# Sheet1.net
KiCad netlist of a schematic drawn in Altium Designer
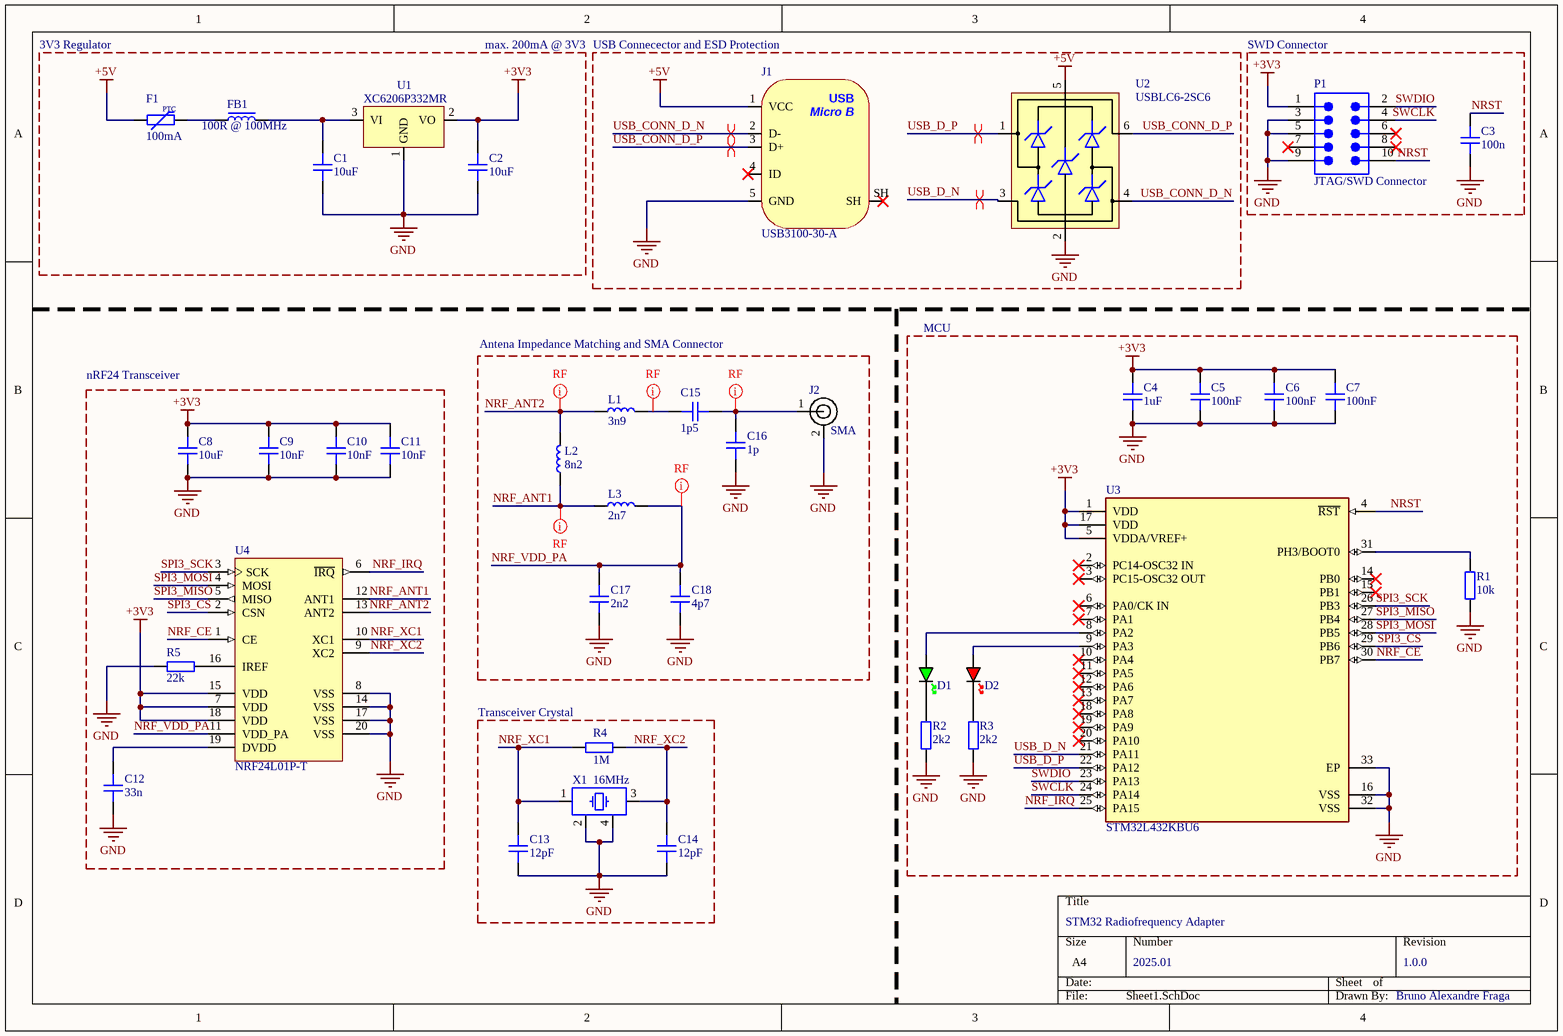
[diagram p0: Sheet1.SchDoc]

(export (version "E")
  (design (tool "Eeschema 10.0.6"))
  (components
    (comp (ref "C1")
      (value "10uF")
      (footprint "CAP_0603")
      (description "Capacitor SMD 0603")
      (libsource (lib "FragasLab") (part "CAP_0603"))
    )
    (comp (ref "C2")
      (value "10uF")
      (footprint "CAP_0603")
      (description "Capacitor SMD 0603")
      (libsource (lib "FragasLab") (part "CAP_0603"))
    )
    (comp (ref "C3")
      (value "100n")
      (footprint "CAP_0402")
      (description "Capacitor SMD 0402")
      (libsource (lib "FragasLab") (part "CAP_0402"))
    )
    (comp (ref "C4")
      (value "1uF")
      (footprint "CAP_0402")
      (description "Capacitor SMD 0402")
      (libsource (lib "FragasLab") (part "CAP_0402"))
    )
    (comp (ref "C5")
      (value "100nF")
      (footprint "CAP_0402")
      (description "Capacitor SMD 0402")
      (libsource (lib "FragasLab") (part "CAP_0402"))
    )
    (comp (ref "C6")
      (value "100nF")
      (footprint "CAP_0402")
      (description "Capacitor SMD 0402")
      (libsource (lib "FragasLab") (part "CAP_0402"))
    )
    (comp (ref "C7")
      (value "100nF")
      (footprint "CAP_0402")
      (description "Capacitor SMD 0402")
      (libsource (lib "FragasLab") (part "CAP_0402"))
    )
    (comp (ref "C8")
      (value "10uF")
      (footprint "CAP_0402")
      (description "Capacitor SMD 0402")
      (libsource (lib "FragasLab") (part "CAP_0402"))
    )
    (comp (ref "C9")
      (value "10nF")
      (footprint "CAP_0402")
      (description "Capacitor SMD 0402")
      (libsource (lib "FragasLab") (part "CAP_0402"))
    )
    (comp (ref "C10")
      (value "10nF")
      (footprint "CAP_0402")
      (description "Capacitor SMD 0402")
      (libsource (lib "FragasLab") (part "CAP_0402"))
    )
    (comp (ref "C11")
      (value "10nF")
      (footprint "CAP_0402")
      (description "Capacitor SMD 0402")
      (libsource (lib "FragasLab") (part "CAP_0402"))
    )
    (comp (ref "C12")
      (value "33n")
      (footprint "CAP_0402")
      (description "Capacitor SMD 0402")
      (libsource (lib "FragasLab") (part "CAP_0402"))
    )
    (comp (ref "C13")
      (value "12pF")
      (footprint "CAP_0402")
      (description "Capacitor SMD 0402")
      (libsource (lib "FragasLab") (part "CAP_0402"))
    )
    (comp (ref "C14")
      (value "12pF")
      (footprint "CAP_0402")
      (description "Capacitor SMD 0402")
      (libsource (lib "FragasLab") (part "CAP_0402"))
    )
    (comp (ref "C15")
      (value "1p5")
      (footprint "CAP_0402")
      (description "Capacitor SMD 0402")
      (libsource (lib "FragasLab") (part "CAP_0402"))
    )
    (comp (ref "C16")
      (value "1p")
      (footprint "CAP_0402")
      (description "Capacitor SMD 0402")
      (libsource (lib "FragasLab") (part "CAP_0402"))
    )
    (comp (ref "C17")
      (value "2n2")
      (footprint "CAP_0402")
      (description "Capacitor SMD 0402")
      (libsource (lib "FragasLab") (part "CAP_0402"))
    )
    (comp (ref "C18")
      (value "4p7")
      (footprint "CAP_0402")
      (description "Capacitor SMD 0402")
      (libsource (lib "FragasLab") (part "CAP_0402"))
    )
    (comp (ref "D1")
      (value "GREEN")
      (footprint "LED_0402_GREEN")
      (description "LED 0402 GREEN SMD")
      (libsource (lib "FragasLab") (part "LED_0402_GREEN"))
    )
    (comp (ref "D2")
      (value "RED")
      (footprint "LED_0402_RED")
      (description "LED 0402 RED SMD")
      (libsource (lib "FragasLab") (part "LED_0402_RED"))
    )
    (comp (ref "F1")
      (value "100mA")
      (footprint "FUSE_1206")
      (description "Fuse PPTC SMD 1206")
      (libsource (lib "FragasLab") (part "FUSE_PPTC_1206"))
    )
    (comp (ref "FB1")
      (value "100R @ 100MHz")
      (footprint "FB_0805")
      (description "Ferrite Bead SMD 0805")
      (libsource (lib "FragasLab") (part "FB_0805"))
    )
    (comp (ref "J1")
      (value "USB3100-30-A")
      (footprint "USB3100-30-A")
      (description "USB Connector Type Micro B 2.0 SMD Reverse Mount")
      (fields (field (name "MANUFACTURER") "GCT"))
      (libsource (lib "FragasLab") (part "USB3100-30-A"))
    )
    (comp (ref "J2")
      (value "SMA")
      (footprint "73251-1150")
      (description "RF Connector 50 Ohms, SMA Jack Receptacle, Edge Mount, .25µm Gold (Au) Plating")
      (fields (field (name "MANUFACTURER") "Molex") (field (name "MANUFACTURER PART NUMBER") "73251-1150"))
      (libsource (lib "FragasLab") (part "73251-1150"))
    )
    (comp (ref "L1")
      (value "3n9")
      (footprint "IND_0402")
      (description "Inductor SMD 0402")
      (libsource (lib "FragasLab") (part "IND_0402"))
    )
    (comp (ref "L2")
      (value "8n2")
      (footprint "IND_0402")
      (description "Inductor SMD 0402")
      (libsource (lib "FragasLab") (part "IND_0402"))
    )
    (comp (ref "L3")
      (value "2n7")
      (footprint "IND_0402")
      (description "Inductor SMD 0402")
      (libsource (lib "FragasLab") (part "IND_0402"))
    )
    (comp (ref "P1")
      (value "JTAG/SWD Connector")
      (footprint "61201021621")
      (libsource (lib "FragasLab") (part "CON-JTAG-Box"))
    )
    (comp (ref "R1")
      (value "10k")
      (footprint "RES_0402")
      (description "Resistor SMD 0402")
      (libsource (lib "FragasLab") (part "RES_0402"))
    )
    (comp (ref "R2")
      (value "2k2")
      (footprint "RES_0603")
      (description "Resistor SMD 0603")
      (libsource (lib "FragasLab") (part "RES_0603"))
    )
    (comp (ref "R3")
      (value "2k2")
      (footprint "RES_0603")
      (description "Resistor SMD 0603")
      (libsource (lib "FragasLab") (part "RES_0603"))
    )
    (comp (ref "R4")
      (value "1M")
      (footprint "RES_0402")
      (description "Resistor SMD 0402")
      (libsource (lib "FragasLab") (part "RES_0402"))
    )
    (comp (ref "R5")
      (value "22k")
      (footprint "RES_0402")
      (description "Resistor SMD 0402")
      (libsource (lib "FragasLab") (part "RES_0402"))
    )
    (comp (ref "U1")
      (value "XC6206P332MR")
      (footprint "SOT95P240X115-3N")
      (description "Linear voltage regulator 250mA;\r\nOutput voltage: 1.5V~5.0V (step size 0.1V).")
      (libsource (lib "FragasLab") (part "XC6206P332MR"))
    )
    (comp (ref "U2")
      (value "USBLC6-2SC6")
      (footprint "SOT-23-6")
      (description "Low-Capacitance ESD Protection USB")
      (fields (field (name "MANUFACTURER") "STMicroelectronics"))
      (libsource (lib "FragasLab") (part "USBLC6-2SC6"))
    )
    (comp (ref "U3")
      (value "STM32L432KBU6")
      (footprint "FP-UFQFPN32-A0B8-MFG")
      (fields
        (field (name "MANUFACTURER") "STMicroelectronics")
        (field (name "OCTOPART") "https://octopart.com/stm32l432kbu6-stmicroelectronics-74568735")
      )
      (libsource (lib "FragasLab") (part "STM32L432KBU6"))
    )
    (comp (ref "U4")
      (value "NRF24L01P-T")
      (footprint "NRSC-QFN-20_L")
      (description "Single Chip Transceiver, 2.4 GHz, 60 mW, 1.9 to 3.6 V, -40 to 85 degC, 20-Pin QFN, RoHS, Tray")
      (fields (field (name "MANUFACTURER") "Nordic Semiconductor"))
      (libsource (lib "FragasLab") (part "nRF24L01"))
    )
    (comp (ref "X1")
      (value "16MHz")
      (footprint "XTAL_2016")
      (description "Crystal SMD 4-Pin 2.0x1.6mm")
      (libsource (lib "FragasLab") (part "XTAL_2016"))
    )
  )
  (nets
    (net (code "1") (name "+3V3") (class "Default")
      (node (ref "C10") (pin "2") (pinfunction "2_2") (pintype "passive"))
      (node (ref "C11") (pin "2") (pinfunction "2_2") (pintype "passive"))
      (node (ref "C2") (pin "1") (pinfunction "1_1") (pintype "passive"))
      (node (ref "C4") (pin "2") (pinfunction "2_2") (pintype "passive"))
      (node (ref "C5") (pin "2") (pinfunction "2_2") (pintype "passive"))
      (node (ref "C6") (pin "2") (pinfunction "2_2") (pintype "passive"))
      (node (ref "C7") (pin "2") (pinfunction "2_2") (pintype "passive"))
      (node (ref "C8") (pin "2") (pinfunction "2_2") (pintype "passive"))
      (node (ref "C9") (pin "2") (pinfunction "2_2") (pintype "passive"))
      (node (ref "P1") (pin "1") (pinfunction "1_1") (pintype "passive"))
      (node (ref "U1") (pin "2") (pinfunction "VO_2") (pintype "passive"))
      (node (ref "U3") (pin "1") (pinfunction "VDD_1") (pintype "power_in"))
      (node (ref "U3") (pin "17") (pinfunction "VDD_17") (pintype "power_in"))
      (node (ref "U3") (pin "5") (pinfunction "VDDA/VREF+_5") (pintype "power_in"))
      (node (ref "U4") (pin "15") (pinfunction "VDD_15") (pintype "power_in"))
      (node (ref "U4") (pin "18") (pinfunction "VDD_18") (pintype "power_in"))
      (node (ref "U4") (pin "7") (pinfunction "VDD_7") (pintype "power_in"))
    )
    (net (code "2") (name "+5V") (class "Default")
      (node (ref "F1") (pin "1") (pinfunction "1_1") (pintype "passive"))
      (node (ref "J1") (pin "1") (pinfunction "VCC_1") (pintype "passive"))
      (node (ref "U2") (pin "5") (pinfunction "VBUS_5") (pintype "power_in"))
    )
    (net (code "3") (name "/NRF_ANT1") (class "Default")
      (node (ref "L2") (pin "1") (pinfunction "1_1") (pintype "passive"))
      (node (ref "L3") (pin "1") (pinfunction "1_1") (pintype "passive"))
      (node (ref "U4") (pin "12") (pinfunction "ANT1_12") (pintype "passive"))
    )
    (net (code "4") (name "/NRF_ANT2") (class "Default")
      (node (ref "L1") (pin "1") (pinfunction "1_1") (pintype "passive"))
      (node (ref "L2") (pin "2") (pinfunction "2_2") (pintype "passive"))
      (node (ref "U4") (pin "13") (pinfunction "ANT2_13") (pintype "passive"))
    )
    (net (code "5") (name "/NRF_CE") (class "Default")
      (node (ref "U3") (pin "30") (pinfunction "PB7_30") (pintype "bidirectional"))
      (node (ref "U4") (pin "1") (pinfunction "CE_1") (pintype "input"))
    )
    (net (code "6") (name "/NRF_IRQ") (class "Default")
      (node (ref "U3") (pin "25") (pinfunction "PA15_25") (pintype "bidirectional"))
      (node (ref "U4") (pin "6") (pinfunction "~{IRQ}_6") (pintype "output"))
    )
    (net (code "7") (name "/NRF_VDD_PA") (class "Default")
      (node (ref "C17") (pin "2") (pinfunction "2_2") (pintype "passive"))
      (node (ref "C18") (pin "2") (pinfunction "2_2") (pintype "passive"))
      (node (ref "L3") (pin "2") (pinfunction "2_2") (pintype "passive"))
      (node (ref "U4") (pin "11") (pinfunction "VDD_PA_11") (pintype "power_in"))
    )
    (net (code "8") (name "/NRF_XC1") (class "Default")
      (node (ref "C13") (pin "2") (pinfunction "2_2") (pintype "passive"))
      (node (ref "R4") (pin "1") (pinfunction "1_1") (pintype "passive"))
      (node (ref "U4") (pin "10") (pinfunction "XC1_10") (pintype "passive"))
      (node (ref "X1") (pin "1") (pinfunction "1_1") (pintype "passive"))
    )
    (net (code "9") (name "/NRF_XC2") (class "Default")
      (node (ref "C14") (pin "2") (pinfunction "2_2") (pintype "passive"))
      (node (ref "R4") (pin "2") (pinfunction "2_2") (pintype "passive"))
      (node (ref "U4") (pin "9") (pinfunction "XC2_9") (pintype "passive"))
      (node (ref "X1") (pin "3") (pinfunction "3_3") (pintype "passive"))
    )
    (net (code "10") (name "/NRST") (class "Default")
      (node (ref "C3") (pin "2") (pinfunction "2_2") (pintype "passive"))
      (node (ref "P1") (pin "10") (pinfunction "10_10") (pintype "passive"))
      (node (ref "U3") (pin "4") (pinfunction "~{RST}_4") (pintype "input"))
    )
    (net (code "11") (name "/SPI3_CS") (class "Default")
      (node (ref "U3") (pin "29") (pinfunction "PB6_29") (pintype "bidirectional"))
      (node (ref "U4") (pin "2") (pinfunction "CSN_2") (pintype "input"))
    )
    (net (code "12") (name "/SPI3_MISO") (class "Default")
      (node (ref "U3") (pin "27") (pinfunction "PB4_27") (pintype "bidirectional"))
      (node (ref "U4") (pin "5") (pinfunction "MISO_5") (pintype "output"))
    )
    (net (code "13") (name "/SPI3_MOSI") (class "Default")
      (node (ref "U3") (pin "28") (pinfunction "PB5_28") (pintype "bidirectional"))
      (node (ref "U4") (pin "4") (pinfunction "MOSI_4") (pintype "input"))
    )
    (net (code "14") (name "/SPI3_SCK") (class "Default")
      (node (ref "U3") (pin "26") (pinfunction "PB3_26") (pintype "bidirectional"))
      (node (ref "U4") (pin "3") (pinfunction "SCK_3") (pintype "input"))
    )
    (net (code "15") (name "/SWCLK") (class "Default")
      (node (ref "P1") (pin "4") (pinfunction "4_4") (pintype "passive"))
      (node (ref "U3") (pin "24") (pinfunction "PA14_24") (pintype "bidirectional"))
    )
    (net (code "16") (name "/SWDIO") (class "Default")
      (node (ref "P1") (pin "2") (pinfunction "2_2") (pintype "passive"))
      (node (ref "U3") (pin "23") (pinfunction "PA13_23") (pintype "bidirectional"))
    )
    (net (code "17") (name "/USB_CONN_D_N") (class "Default")
      (node (ref "J1") (pin "2") (pinfunction "D-_2") (pintype "passive"))
      (node (ref "U2") (pin "4") (pinfunction "IO2_4") (pintype "bidirectional"))
    )
    (net (code "18") (name "/USB_CONN_D_P") (class "Default")
      (node (ref "J1") (pin "3") (pinfunction "D+_3") (pintype "passive"))
      (node (ref "U2") (pin "6") (pinfunction "IO1_6") (pintype "bidirectional"))
    )
    (net (code "19") (name "/USB_D_N") (class "Default")
      (node (ref "U2") (pin "3") (pinfunction "IO2_3") (pintype "bidirectional"))
      (node (ref "U3") (pin "21") (pinfunction "PA11_21") (pintype "bidirectional"))
    )
    (net (code "20") (name "/USB_D_P") (class "Default")
      (node (ref "U2") (pin "1") (pinfunction "IO1_1") (pintype "bidirectional"))
      (node (ref "U3") (pin "22") (pinfunction "PA12_22") (pintype "bidirectional"))
    )
    (net (code "21") (name "GND") (class "Default")
      (node (ref "C1") (pin "2") (pinfunction "2_2") (pintype "passive"))
      (node (ref "C10") (pin "1") (pinfunction "1_1") (pintype "passive"))
      (node (ref "C11") (pin "1") (pinfunction "1_1") (pintype "passive"))
      (node (ref "C12") (pin "1") (pinfunction "1_1") (pintype "passive"))
      (node (ref "C13") (pin "1") (pinfunction "1_1") (pintype "passive"))
      (node (ref "C14") (pin "1") (pinfunction "1_1") (pintype "passive"))
      (node (ref "C16") (pin "1") (pinfunction "1_1") (pintype "passive"))
      (node (ref "C17") (pin "1") (pinfunction "1_1") (pintype "passive"))
      (node (ref "C18") (pin "1") (pinfunction "1_1") (pintype "passive"))
      (node (ref "C2") (pin "2") (pinfunction "2_2") (pintype "passive"))
      (node (ref "C3") (pin "1") (pinfunction "1_1") (pintype "passive"))
      (node (ref "C4") (pin "1") (pinfunction "1_1") (pintype "passive"))
      (node (ref "C5") (pin "1") (pinfunction "1_1") (pintype "passive"))
      (node (ref "C6") (pin "1") (pinfunction "1_1") (pintype "passive"))
      (node (ref "C7") (pin "1") (pinfunction "1_1") (pintype "passive"))
      (node (ref "C8") (pin "1") (pinfunction "1_1") (pintype "passive"))
      (node (ref "C9") (pin "1") (pinfunction "1_1") (pintype "passive"))
      (node (ref "J1") (pin "5") (pinfunction "GND_5") (pintype "passive"))
      (node (ref "J2") (pin "2") (pinfunction "2_2") (pintype "passive"))
      (node (ref "P1") (pin "3") (pinfunction "3_3") (pintype "passive"))
      (node (ref "P1") (pin "5") (pinfunction "5_5") (pintype "passive"))
      (node (ref "P1") (pin "9") (pinfunction "9_9") (pintype "passive"))
      (node (ref "R1") (pin "1") (pinfunction "1_1") (pintype "passive"))
      (node (ref "R2") (pin "1") (pinfunction "1_1") (pintype "passive"))
      (node (ref "R3") (pin "1") (pinfunction "1_1") (pintype "passive"))
      (node (ref "R5") (pin "2") (pinfunction "2_2") (pintype "passive"))
      (node (ref "U1") (pin "1") (pinfunction "GND_1") (pintype "passive"))
      (node (ref "U2") (pin "2") (pinfunction "GND_2") (pintype "power_in"))
      (node (ref "U3") (pin "16") (pinfunction "VSS_16") (pintype "power_in"))
      (node (ref "U3") (pin "32") (pinfunction "VSS_32") (pintype "power_in"))
      (node (ref "U3") (pin "33") (pinfunction "EP_33") (pintype "power_in"))
      (node (ref "U4") (pin "14") (pinfunction "VSS_14") (pintype "power_in"))
      (node (ref "U4") (pin "17") (pinfunction "VSS_17") (pintype "power_in"))
      (node (ref "U4") (pin "20") (pinfunction "VSS_20") (pintype "power_in"))
      (node (ref "U4") (pin "8") (pinfunction "VSS_8") (pintype "power_in"))
      (node (ref "X1") (pin "2") (pinfunction "2_2") (pintype "passive"))
      (node (ref "X1") (pin "4") (pinfunction "4_4") (pintype "passive"))
    )
    (net (code "22") (name "Net-(C15-Pad1)") (class "Default")
      (node (ref "C15") (pin "1") (pinfunction "1_1") (pintype "passive"))
      (node (ref "L1") (pin "2") (pinfunction "2_2") (pintype "passive"))
    )
    (net (code "23") (name "Net-(C15-Pad2)") (class "Default")
      (node (ref "C15") (pin "2") (pinfunction "2_2") (pintype "passive"))
      (node (ref "C16") (pin "2") (pinfunction "2_2") (pintype "passive"))
      (node (ref "J2") (pin "1") (pinfunction "1_1") (pintype "passive"))
    )
    (net (code "24") (name "Net-(D1-PadK)") (class "Default")
      (node (ref "D1") (pin "K") (pinfunction "K_K") (pintype "passive"))
      (node (ref "R2") (pin "2") (pinfunction "2_2") (pintype "passive"))
    )
    (net (code "25") (name "Net-(D2-PadK)") (class "Default")
      (node (ref "D2") (pin "K") (pinfunction "K_K") (pintype "passive"))
      (node (ref "R3") (pin "2") (pinfunction "2_2") (pintype "passive"))
    )
    (net (code "26") (name "Net-(F1-Pad2)") (class "Default")
      (node (ref "F1") (pin "2") (pinfunction "2_2") (pintype "passive"))
      (node (ref "FB1") (pin "1") (pinfunction "1_1") (pintype "passive"))
    )
    (net (code "27") (name "Net-(U1-VI)") (class "Default")
      (node (ref "C1") (pin "1") (pinfunction "1_1") (pintype "passive"))
      (node (ref "FB1") (pin "2") (pinfunction "2_2") (pintype "passive"))
      (node (ref "U1") (pin "3") (pinfunction "VI_3") (pintype "passive"))
    )
    (net (code "28") (name "Net-(U3-PA2)") (class "Default")
      (node (ref "D1") (pin "A") (pinfunction "A_A") (pintype "passive"))
      (node (ref "U3") (pin "8") (pinfunction "PA2_8") (pintype "bidirectional"))
    )
    (net (code "29") (name "Net-(U3-PA3)") (class "Default")
      (node (ref "D2") (pin "A") (pinfunction "A_A") (pintype "passive"))
      (node (ref "U3") (pin "9") (pinfunction "PA3_9") (pintype "bidirectional"))
    )
    (net (code "30") (name "Net-(U3-PH3{slash}BOOT0)") (class "Default")
      (node (ref "R1") (pin "2") (pinfunction "2_2") (pintype "passive"))
      (node (ref "U3") (pin "31") (pinfunction "PH3/BOOT0_31") (pintype "bidirectional"))
    )
    (net (code "31") (name "Net-(U4-DVDD)") (class "Default")
      (node (ref "C12") (pin "2") (pinfunction "2_2") (pintype "passive"))
      (node (ref "U4") (pin "19") (pinfunction "DVDD_19") (pintype "power_in"))
    )
    (net (code "32") (name "Net-(U4-IREF)") (class "Default")
      (node (ref "R5") (pin "1") (pinfunction "1_1") (pintype "passive"))
      (node (ref "U4") (pin "16") (pinfunction "IREF_16") (pintype "passive"))
    )
    (net (code "33") (name "unconnected-(J1-ID-Pad4)") (class "Default")
      (node (ref "J1") (pin "4") (pinfunction "ID_4") (pintype "passive+no_connect"))
    )
    (net (code "34") (name "unconnected-(J1-PadSH)") (class "Default")
      (node (ref "J1") (pin "SH") (pinfunction "SH_SH") (pintype "passive+no_connect"))
    )
    (net (code "35") (name "unconnected-(P1-Pad6)") (class "Default")
      (node (ref "P1") (pin "6") (pinfunction "6_6") (pintype "passive+no_connect"))
    )
    (net (code "36") (name "unconnected-(P1-Pad7)") (class "Default")
      (node (ref "P1") (pin "7") (pinfunction "7_7") (pintype "passive+no_connect"))
    )
    (net (code "37") (name "unconnected-(P1-Pad8)") (class "Default")
      (node (ref "P1") (pin "8") (pinfunction "8_8") (pintype "passive+no_connect"))
    )
    (net (code "38") (name "unconnected-(U3-PA0{slash}CK_IN-Pad6)") (class "Default")
      (node (ref "U3") (pin "6") (pinfunction "PA0/CK_IN_6") (pintype "bidirectional+no_connect"))
    )
    (net (code "39") (name "unconnected-(U3-PA1-Pad7)") (class "Default")
      (node (ref "U3") (pin "7") (pinfunction "PA1_7") (pintype "bidirectional+no_connect"))
    )
    (net (code "40") (name "unconnected-(U3-PA4-Pad10)") (class "Default")
      (node (ref "U3") (pin "10") (pinfunction "PA4_10") (pintype "bidirectional+no_connect"))
    )
    (net (code "41") (name "unconnected-(U3-PA5-Pad11)") (class "Default")
      (node (ref "U3") (pin "11") (pinfunction "PA5_11") (pintype "bidirectional+no_connect"))
    )
    (net (code "42") (name "unconnected-(U3-PA6-Pad12)") (class "Default")
      (node (ref "U3") (pin "12") (pinfunction "PA6_12") (pintype "bidirectional+no_connect"))
    )
    (net (code "43") (name "unconnected-(U3-PA7-Pad13)") (class "Default")
      (node (ref "U3") (pin "13") (pinfunction "PA7_13") (pintype "bidirectional+no_connect"))
    )
    (net (code "44") (name "unconnected-(U3-PA8-Pad18)") (class "Default")
      (node (ref "U3") (pin "18") (pinfunction "PA8_18") (pintype "bidirectional+no_connect"))
    )
    (net (code "45") (name "unconnected-(U3-PA9-Pad19)") (class "Default")
      (node (ref "U3") (pin "19") (pinfunction "PA9_19") (pintype "bidirectional+no_connect"))
    )
    (net (code "46") (name "unconnected-(U3-PA10-Pad20)") (class "Default")
      (node (ref "U3") (pin "20") (pinfunction "PA10_20") (pintype "bidirectional+no_connect"))
    )
    (net (code "47") (name "unconnected-(U3-PB0-Pad14)") (class "Default")
      (node (ref "U3") (pin "14") (pinfunction "PB0_14") (pintype "bidirectional+no_connect"))
    )
    (net (code "48") (name "unconnected-(U3-PB1-Pad15)") (class "Default")
      (node (ref "U3") (pin "15") (pinfunction "PB1_15") (pintype "bidirectional+no_connect"))
    )
    (net (code "49") (name "unconnected-(U3-PC14-OSC32_IN-Pad2)") (class "Default")
      (node (ref "U3") (pin "2") (pinfunction "PC14-OSC32_IN_2") (pintype "bidirectional+no_connect"))
    )
    (net (code "50") (name "unconnected-(U3-PC15-OSC32_OUT-Pad3)") (class "Default")
      (node (ref "U3") (pin "3") (pinfunction "PC15-OSC32_OUT_3") (pintype "bidirectional+no_connect"))
    )
  )
)
